# No_Transistor_LED.net
KiCad netlist of a schematic drawn in Altium Designer
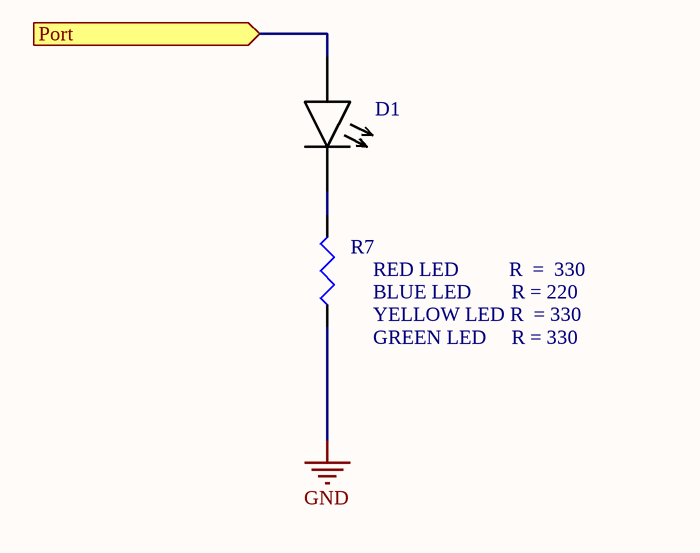
[diagram p0: No_Transistor_LED.SchDoc]

(export (version "E")
  (design (tool "Eeschema 10.0.6"))
  (components
    (comp (ref "D1")
      (value "LED_R")
      (footprint "0402 footprint")
      (libsource (lib "AvionicsParts") (part "LED_R"))
    )
    (comp (ref "R7")
      (value "Res3")
      (description "Resistor")
      (fields (field (name "PUBLISHER") "Altium Limited"))
      (libsource (lib "Miscellaneous Devices") (part "Res3"))
    )
  )
  (nets
    (net (code "1") (name "/Port") (class "Default")
      (node (ref "D1") (pin "1") (pinfunction "1_1") (pintype "passive"))
    )
    (net (code "2") (name "GND") (class "Default")
      (node (ref "R7") (pin "1") (pinfunction "1_1") (pintype "passive"))
    )
    (net (code "3") (name "Net-(D1-Pad2)") (class "Default")
      (node (ref "D1") (pin "2") (pinfunction "2_2") (pintype "passive"))
      (node (ref "R7") (pin "2") (pinfunction "2_2") (pintype "passive"))
    )
  )
)
